# MSP430.net
KiCad netlist of a schematic drawn in Altium Designer
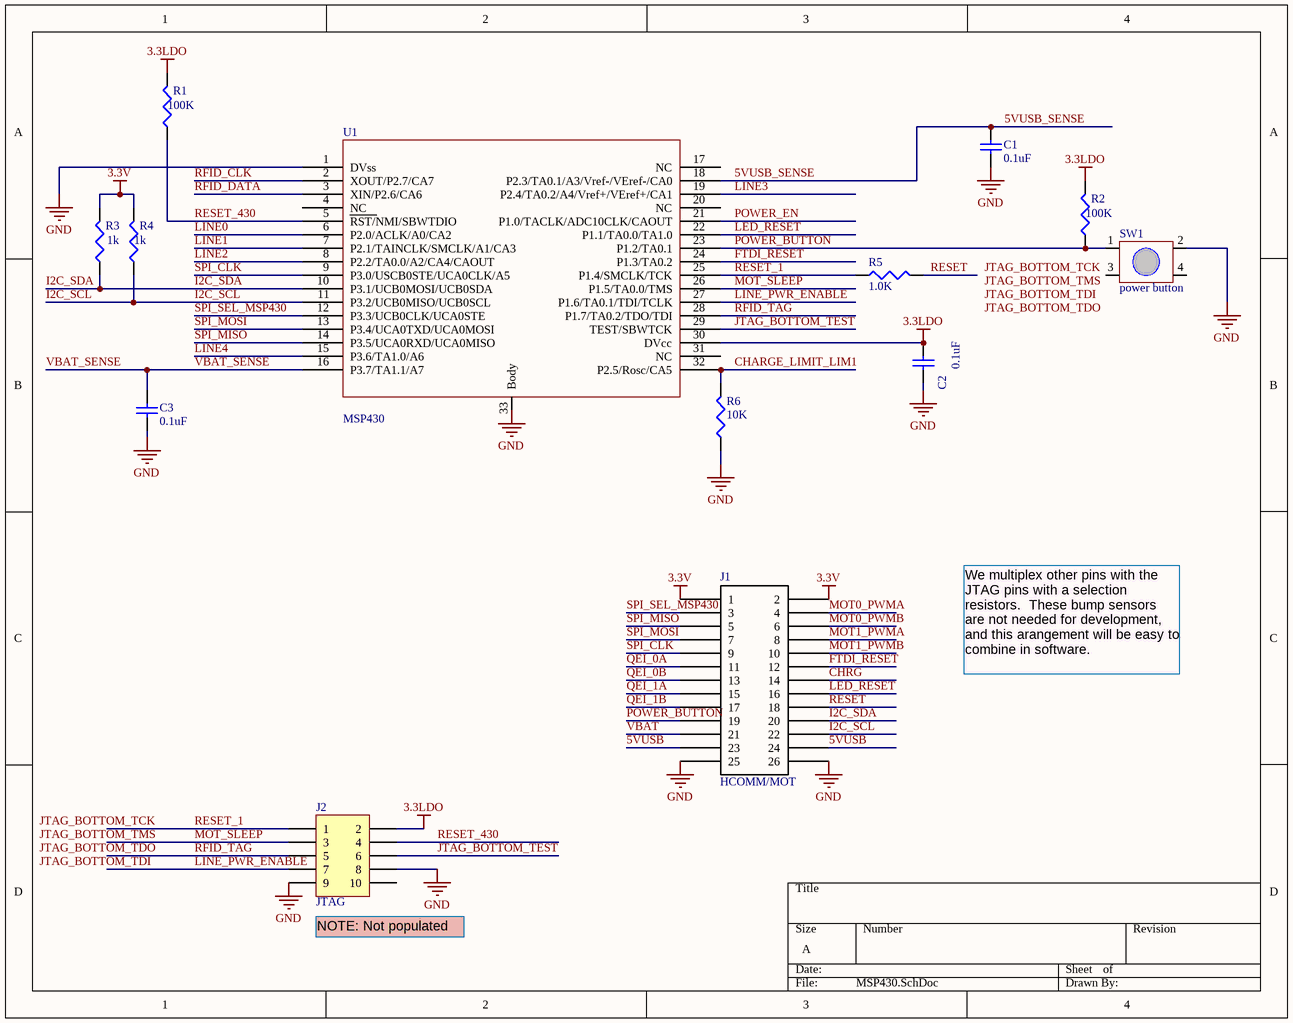
[diagram p0: MSP430.SchDoc]

(export (version "E")
  (design (tool "Eeschema 10.0.6"))
  (components
    (comp (ref "C1")
      (value "0.1uF")
      (footprint "CAPC1005L")
      (description "Capacitor (Semiconductor SIM Model)")
      (fields (field (name "Comment") "Cap Semi") (field (name "PUBLISHER") "Altium Limited"))
      (libsource (lib "Miscellaneous Devices") (part "Cap Semi"))
    )
    (comp (ref "C2")
      (value "0.1uF")
      (footprint "CAPC1005L")
      (description "Capacitor (Semiconductor SIM Model)")
      (fields (field (name "Comment") "Cap Semi") (field (name "PUBLISHER") "Altium Limited"))
      (libsource (lib "Miscellaneous Devices") (part "Cap Semi"))
    )
    (comp (ref "C3")
      (value "0.1uF")
      (footprint "CAPC1005L")
      (description "Capacitor (Semiconductor SIM Model)")
      (fields (field (name "Comment") "Cap Semi") (field (name "PUBLISHER") "Altium Limited"))
      (libsource (lib "Miscellaneous Devices") (part "Cap Semi"))
    )
    (comp (ref "J1")
      (value "HCOMM/MOT")
      (footprint "HeaderSM 13x2")
      (description "Header, 2X20, 50mil, IDC")
      (libsource (lib "mrone") (part "HCOMM/HMOT"))
    )
    (comp (ref "J2")
      (value "JTAG")
      (footprint "HDR2X5")
      (description "Header, 5-Pin, Dual row")
      (fields (field (name "PUBLISHER") "Altium Limited"))
      (libsource (lib "Miscellaneous Connectors") (part "Header 5X2"))
    )
    (comp (ref "R1")
      (value "100K")
      (footprint "RESC1608L")
      (description "Resistor")
      (fields (field (name "Comment") "Res3") (field (name "PUBLISHER") "Altium Limited"))
      (libsource (lib "Miscellaneous Devices") (part "Res3"))
    )
    (comp (ref "R2")
      (value "100K")
      (footprint "RESC1608L")
      (description "Resistor")
      (fields (field (name "Comment") "Res3") (field (name "PUBLISHER") "Altium Limited"))
      (libsource (lib "Miscellaneous Devices") (part "Res3"))
    )
    (comp (ref "R3")
      (value "1k")
      (footprint "RESC1608L")
      (description "Resistor")
      (fields (field (name "Comment") "Res3") (field (name "PUBLISHER") "Altium Limited"))
      (libsource (lib "Miscellaneous Devices") (part "Res3"))
    )
    (comp (ref "R4")
      (value "1k")
      (footprint "RESC1608L")
      (description "Resistor")
      (fields (field (name "Comment") "Res3") (field (name "PUBLISHER") "Altium Limited"))
      (libsource (lib "Miscellaneous Devices") (part "Res3"))
    )
    (comp (ref "R5")
      (value "1.0K")
      (footprint "J1-0603")
      (description "Resistor")
      (fields (field (name "Comment") "Res3") (field (name "PUBLISHER") "Altium Limited"))
      (libsource (lib "Miscellaneous Devices") (part "Res3"))
    )
    (comp (ref "R6")
      (value "10K")
      (footprint "RESC1608L")
      (description "Resistor")
      (fields (field (name "Comment") "Res3") (field (name "PUBLISHER") "Altium Limited"))
      (libsource (lib "Miscellaneous Devices") (part "Res3"))
    )
    (comp (ref "SW1")
      (value "power button")
      (footprint "SwitchTall-TL330")
      (libsource (lib "mrone") (part "Switch-TL330"))
    )
    (comp (ref "U1")
      (value "MSP430")
      (footprint "MSP430_32PIN")
      (libsource (lib "mrone") (part "MSP430_32pin"))
    )
  )
  (nets
    (net (code "1") (name "/5VUSB") (class "Default")
      (node (ref "J1") (pin "23") (pinfunction "23_23") (pintype "passive"))
      (node (ref "J1") (pin "24") (pinfunction "24_24") (pintype "passive"))
    )
    (net (code "2") (name "/5VUSB_SENSE") (class "Default")
      (node (ref "C1") (pin "2") (pinfunction "2_2") (pintype "passive"))
      (node (ref "U1") (pin "18") (pinfunction "P2.3/TA0.1/A3/Vref-/VEref-/CA0_18") (pintype "passive"))
    )
    (net (code "3") (name "/CHARGE_LIMIT_LIM1") (class "Default")
      (node (ref "R6") (pin "2") (pinfunction "2_2") (pintype "passive"))
      (node (ref "U1") (pin "32") (pinfunction "P2.5/Rosc/CA5_32") (pintype "passive"))
    )
    (net (code "4") (name "/CHRG") (class "Default")
      (node (ref "J1") (pin "14") (pinfunction "14_14") (pintype "passive"))
    )
    (net (code "5") (name "/FTDI_RESET") (class "Default")
      (node (ref "J1") (pin "12") (pinfunction "12_12") (pintype "passive"))
      (node (ref "U1") (pin "24") (pinfunction "P1.3/TA0.2_24") (pintype "passive"))
    )
    (net (code "6") (name "/I2C_SCL") (class "Default")
      (node (ref "J1") (pin "22") (pinfunction "22_22") (pintype "passive"))
      (node (ref "R4") (pin "1") (pinfunction "1_1") (pintype "passive"))
      (node (ref "U1") (pin "11") (pinfunction "P3.2/UCB0MISO/UCB0SCL_11") (pintype "passive"))
    )
    (net (code "7") (name "/I2C_SDA") (class "Default")
      (node (ref "J1") (pin "20") (pinfunction "20_20") (pintype "passive"))
      (node (ref "R3") (pin "1") (pinfunction "1_1") (pintype "passive"))
      (node (ref "U1") (pin "10") (pinfunction "P3.1/UCB0MOSI/UCB0SDA_10") (pintype "passive"))
    )
    (net (code "11") (name "/JTAG_BOTTOM_TEST") (class "Default")
      (node (ref "J2") (pin "6") (pinfunction "6_6") (pintype "passive"))
      (node (ref "U1") (pin "29") (pinfunction "TEST/SBWTCK_29") (pintype "passive"))
    )
    (net (code "13") (name "/LED_RESET") (class "Default")
      (node (ref "J1") (pin "16") (pinfunction "16_16") (pintype "passive"))
      (node (ref "U1") (pin "22") (pinfunction "P1.1/TA0.0/TA1.0_22") (pintype "passive"))
    )
    (net (code "14") (name "/LINE0") (class "Default")
      (node (ref "U1") (pin "6") (pinfunction "P2.0/ACLK/A0/CA2_6") (pintype "passive"))
    )
    (net (code "15") (name "/LINE1") (class "Default")
      (node (ref "U1") (pin "7") (pinfunction "P2.1/TAINCLK/SMCLK/A1/CA3_7") (pintype "passive"))
    )
    (net (code "16") (name "/LINE2") (class "Default")
      (node (ref "U1") (pin "8") (pinfunction "P2.2/TA0.0/A2/CA4/CAOUT_8") (pintype "passive"))
    )
    (net (code "17") (name "/LINE3") (class "Default")
      (node (ref "U1") (pin "19") (pinfunction "P2.4/TA0.2/A4/Vref+/VEref+/CA1_19") (pintype "passive"))
    )
    (net (code "18") (name "/LINE4") (class "Default")
      (node (ref "U1") (pin "15") (pinfunction "P3.6/TA1.0/A6_15") (pintype "passive"))
    )
    (net (code "19") (name "/LINE_PWR_ENABLE") (class "Default")
      (node (ref "J2") (pin "7") (pinfunction "7_7") (pintype "passive"))
      (node (ref "U1") (pin "27") (pinfunction "P1.6/TA0.1/TDI/TCLK_27") (pintype "passive"))
    )
    (net (code "20") (name "/MOT0_PWMA") (class "Default")
      (node (ref "J1") (pin "4") (pinfunction "4_4") (pintype "passive"))
    )
    (net (code "21") (name "/MOT0_PWMB") (class "Default")
      (node (ref "J1") (pin "6") (pinfunction "6_6") (pintype "passive"))
    )
    (net (code "22") (name "/MOT1_PWMA") (class "Default")
      (node (ref "J1") (pin "8") (pinfunction "8_8") (pintype "passive"))
    )
    (net (code "23") (name "/MOT1_PWMB") (class "Default")
      (node (ref "J1") (pin "10") (pinfunction "10_10") (pintype "passive"))
    )
    (net (code "24") (name "/MOT_SLEEP") (class "Default")
      (node (ref "J2") (pin "3") (pinfunction "3_3") (pintype "passive"))
      (node (ref "U1") (pin "26") (pinfunction "P1.5/TA0.0/TMS_26") (pintype "passive"))
    )
    (net (code "25") (name "/POWER_BUTTON") (class "Default")
      (node (ref "J1") (pin "19") (pinfunction "19_19") (pintype "passive"))
      (node (ref "R2") (pin "1") (pinfunction "1_1") (pintype "passive"))
      (node (ref "SW1") (pin "1") (pinfunction "1_1") (pintype "passive"))
      (node (ref "U1") (pin "23") (pinfunction "P1.2/TA0.1_23") (pintype "passive"))
    )
    (net (code "26") (name "/POWER_EN") (class "Default")
      (node (ref "U1") (pin "21") (pinfunction "P1.0/TACLK/ADC10CLK/CAOUT_21") (pintype "passive"))
    )
    (net (code "27") (name "/QEI_0A") (class "Default")
      (node (ref "J1") (pin "11") (pinfunction "11_11") (pintype "passive"))
    )
    (net (code "28") (name "/QEI_0B") (class "Default")
      (node (ref "J1") (pin "13") (pinfunction "13_13") (pintype "passive"))
    )
    (net (code "29") (name "/QEI_1A") (class "Default")
      (node (ref "J1") (pin "15") (pinfunction "15_15") (pintype "passive"))
    )
    (net (code "30") (name "/QEI_1B") (class "Default")
      (node (ref "J1") (pin "17") (pinfunction "17_17") (pintype "passive"))
    )
    (net (code "31") (name "/RESET") (class "Default")
      (node (ref "J1") (pin "18") (pinfunction "18_18") (pintype "passive"))
      (node (ref "R5") (pin "2") (pinfunction "2_2") (pintype "passive"))
    )
    (net (code "32") (name "/RESET_1") (class "Default")
      (node (ref "J2") (pin "1") (pinfunction "1_1") (pintype "passive"))
      (node (ref "R5") (pin "1") (pinfunction "1_1") (pintype "passive"))
      (node (ref "U1") (pin "25") (pinfunction "P1.4/SMCLK/TCK_25") (pintype "passive"))
    )
    (net (code "33") (name "/RESET_430") (class "Default")
      (node (ref "J2") (pin "4") (pinfunction "4_4") (pintype "passive"))
      (node (ref "R1") (pin "1") (pinfunction "1_1") (pintype "passive"))
      (node (ref "U1") (pin "5") (pinfunction "RST/NMI/SBWTDIO_5") (pintype "passive"))
    )
    (net (code "34") (name "/RFID_CLK") (class "Default")
      (node (ref "U1") (pin "2") (pinfunction "XOUT/P2.7/CA7_2") (pintype "passive"))
    )
    (net (code "35") (name "/RFID_DATA") (class "Default")
      (node (ref "U1") (pin "3") (pinfunction "XIN/P2.6/CA6_3") (pintype "passive"))
    )
    (net (code "36") (name "/RFID_TAG") (class "Default")
      (node (ref "J2") (pin "5") (pinfunction "5_5") (pintype "passive"))
      (node (ref "U1") (pin "28") (pinfunction "P1.7/TA0.2/TDO/TDI_28") (pintype "passive"))
    )
    (net (code "37") (name "/SPI_CLK") (class "Default")
      (node (ref "J1") (pin "9") (pinfunction "9_9") (pintype "passive"))
      (node (ref "U1") (pin "9") (pinfunction "P3.0/USCB0STE/UCA0CLK/A5_9") (pintype "passive"))
    )
    (net (code "38") (name "/SPI_MISO") (class "Default")
      (node (ref "J1") (pin "5") (pinfunction "5_5") (pintype "passive"))
      (node (ref "U1") (pin "14") (pinfunction "P3.5/UCA0RXD/UCA0MISO_14") (pintype "passive"))
    )
    (net (code "39") (name "/SPI_MOSI") (class "Default")
      (node (ref "J1") (pin "7") (pinfunction "7_7") (pintype "passive"))
      (node (ref "U1") (pin "13") (pinfunction "P3.4/UCA0TXD/UCA0MOSI_13") (pintype "passive"))
    )
    (net (code "40") (name "/SPI_SEL_MSP430") (class "Default")
      (node (ref "J1") (pin "3") (pinfunction "3_3") (pintype "passive"))
      (node (ref "U1") (pin "12") (pinfunction "P3.3/UCB0CLK/UCA0STE_12") (pintype "passive"))
    )
    (net (code "41") (name "/VBAT") (class "Default")
      (node (ref "J1") (pin "21") (pinfunction "21_21") (pintype "passive"))
    )
    (net (code "42") (name "/VBAT_SENSE") (class "Default")
      (node (ref "C3") (pin "2") (pinfunction "2_2") (pintype "passive"))
      (node (ref "U1") (pin "16") (pinfunction "P3.7/TA1.1/A7_16") (pintype "passive"))
    )
    (net (code "43") (name "3.3LDO") (class "Default")
      (node (ref "C2") (pin "2") (pinfunction "2_2") (pintype "passive"))
      (node (ref "J2") (pin "2") (pinfunction "2_2") (pintype "passive"))
      (node (ref "R1") (pin "2") (pinfunction "2_2") (pintype "passive"))
      (node (ref "R2") (pin "2") (pinfunction "2_2") (pintype "passive"))
      (node (ref "U1") (pin "30") (pinfunction "DVcc_30") (pintype "passive"))
    )
    (net (code "44") (name "3.3V") (class "Default")
      (node (ref "J1") (pin "1") (pinfunction "1_1") (pintype "passive"))
      (node (ref "J1") (pin "2") (pinfunction "2_2") (pintype "passive"))
      (node (ref "R3") (pin "2") (pinfunction "2_2") (pintype "passive"))
      (node (ref "R4") (pin "2") (pinfunction "2_2") (pintype "passive"))
    )
    (net (code "45") (name "GND") (class "Default")
      (node (ref "C1") (pin "1") (pinfunction "1_1") (pintype "passive"))
      (node (ref "C2") (pin "1") (pinfunction "1_1") (pintype "passive"))
      (node (ref "C3") (pin "1") (pinfunction "1_1") (pintype "passive"))
      (node (ref "J1") (pin "25") (pinfunction "25_25") (pintype "passive"))
      (node (ref "J1") (pin "26") (pinfunction "26_26") (pintype "passive"))
      (node (ref "J2") (pin "8") (pinfunction "8_8") (pintype "passive"))
      (node (ref "J2") (pin "9") (pinfunction "9_9") (pintype "passive"))
      (node (ref "R6") (pin "1") (pinfunction "1_1") (pintype "passive"))
      (node (ref "SW1") (pin "2") (pinfunction "2_2") (pintype "passive"))
      (node (ref "U1") (pin "1") (pinfunction "DVss_1") (pintype "passive"))
      (node (ref "U1") (pin "33") (pinfunction "Body_33") (pintype "power_in"))
    )
    (net (code "46") (name "unconnected-(J2-Pad10)") (class "Default")
      (node (ref "J2") (pin "10") (pinfunction "10_10") (pintype "passive"))
    )
    (net (code "47") (name "unconnected-(SW1-Pad3)") (class "Default")
      (node (ref "SW1") (pin "3") (pinfunction "3_3") (pintype "passive"))
    )
    (net (code "48") (name "unconnected-(SW1-Pad4)") (class "Default")
      (node (ref "SW1") (pin "4") (pinfunction "4_4") (pintype "passive"))
    )
    (net (code "49") (name "unconnected-(U1-NC-Pad4)") (class "Default")
      (node (ref "U1") (pin "4") (pinfunction "NC_4") (pintype "passive"))
    )
    (net (code "50") (name "unconnected-(U1-NC-Pad17)") (class "Default")
      (node (ref "U1") (pin "17") (pinfunction "NC_17") (pintype "passive"))
    )
    (net (code "51") (name "unconnected-(U1-NC-Pad20)") (class "Default")
      (node (ref "U1") (pin "20") (pinfunction "NC_20") (pintype "passive"))
    )
    (net (code "52") (name "unconnected-(U1-NC-Pad31)") (class "Default")
      (node (ref "U1") (pin "31") (pinfunction "NC_31") (pintype "passive"))
    )
  )
)
